# LooRollSensorTop.net
KiCad netlist of a schematic drawn in EAGLE
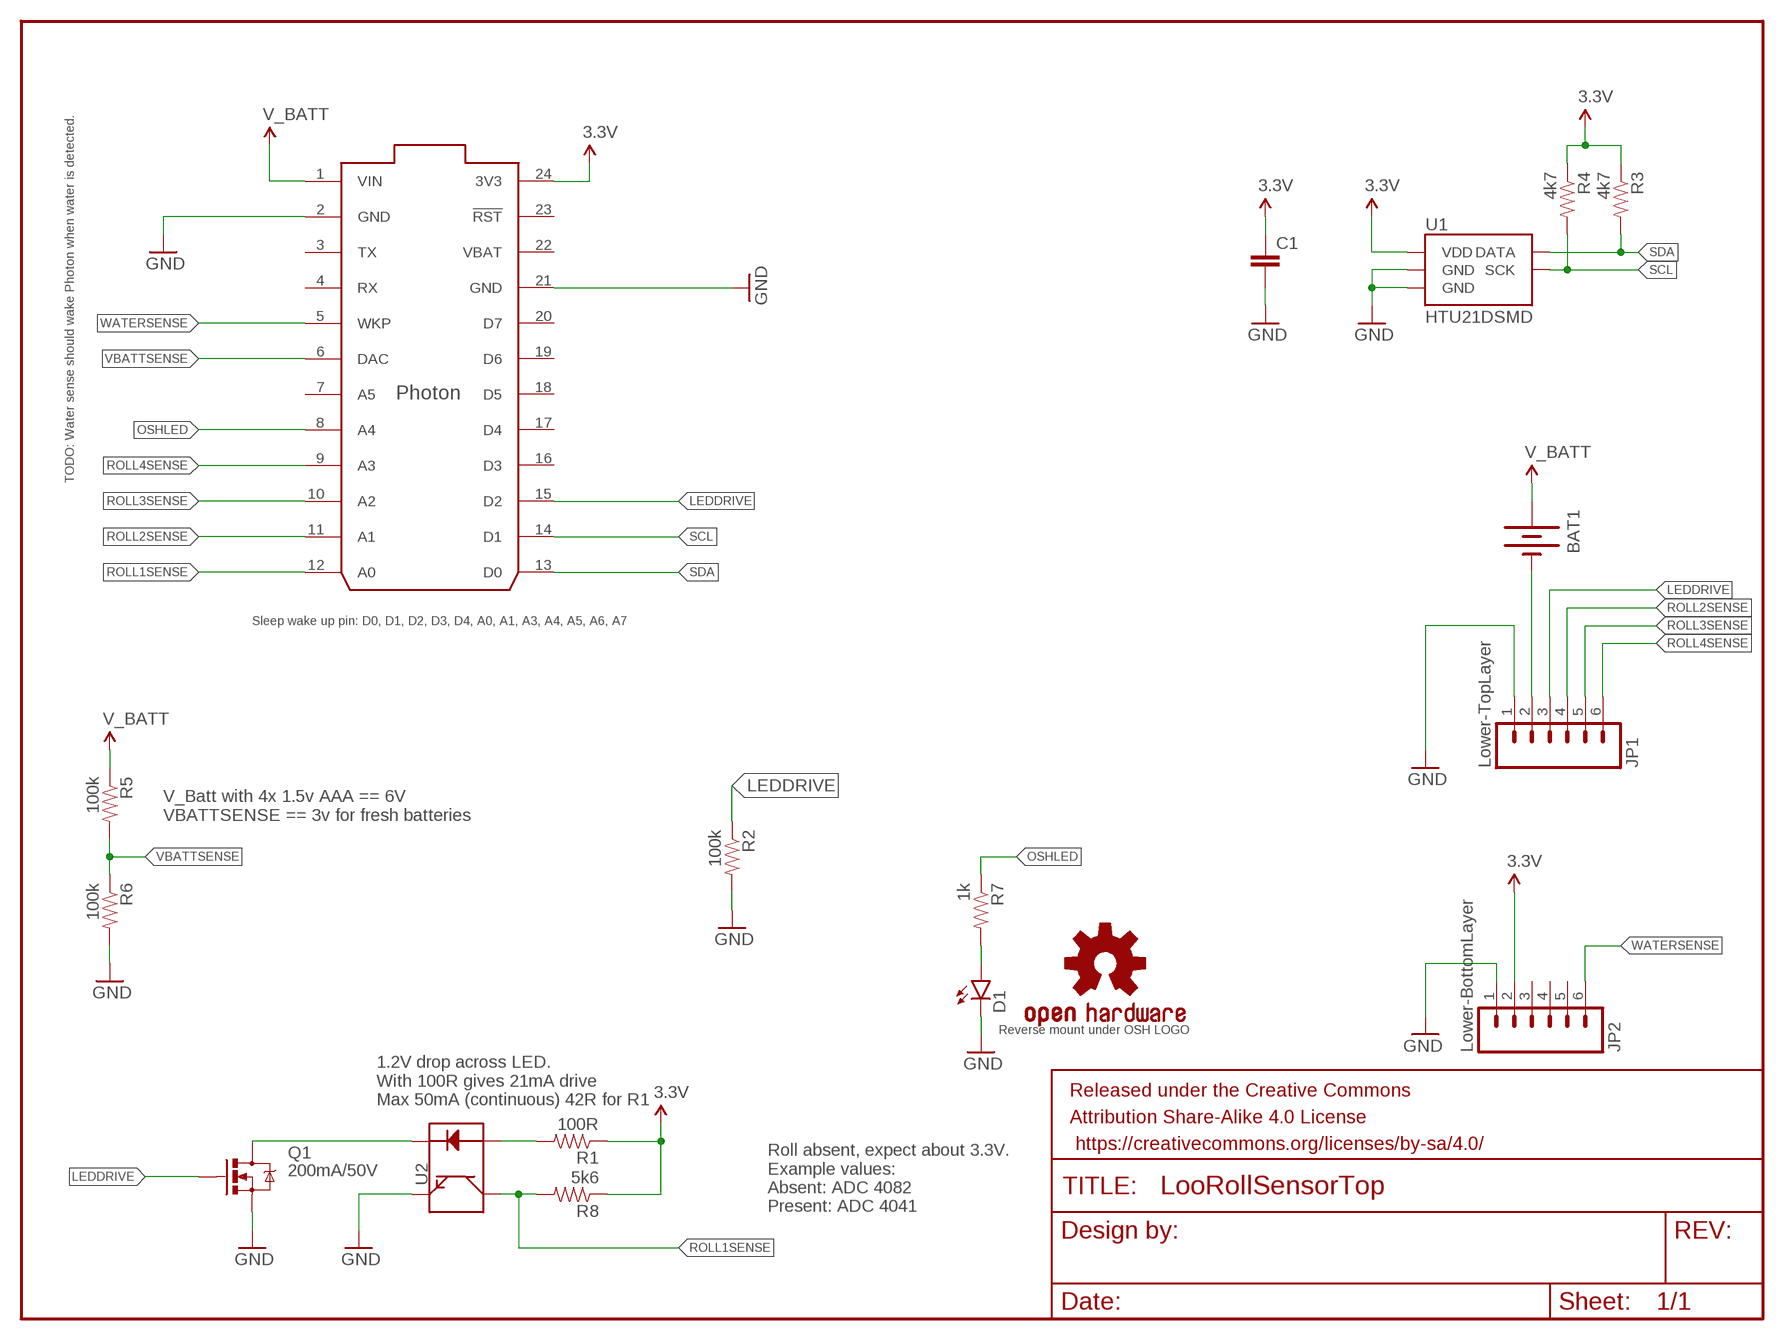
[diagram p0: schematic, sheet 1]

(export (version "E")
  (design (tool "Eeschema 10.0.6"))
  (components
    (comp (ref "BAT1")
      (value "BATTERYAA-PANEL")
      (footprint "eagle-import:BATTERY-AA-PANEL")
      (libsource (lib "eagle-import") (part "BATTERYAA-PANEL"))
    )
    (comp (ref "C1")
      (value "CAP0805")
      (footprint "eagle-import:0805")
      (libsource (lib "eagle-import") (part "CAP0805"))
    )
    (comp (ref "D1")
      (value "LED1206-BOTTOM")
      (footprint "eagle-import:LED-1206-BOTTOM")
      (libsource (lib "eagle-import") (part "LED1206-BOTTOM"))
    )
    (comp (ref "FRAME1")
      (value "FRAME-LETTER")
      (footprint "eagle-import:CREATIVE_COMMONS")
      (libsource (lib "eagle-import") (part "FRAME-LETTER"))
    )
    (comp (ref "JP1")
      (value "Lower-TopLayer")
      (footprint "eagle-import:1X06-SMD_EDGE")
      (libsource (lib "eagle-import") (part "M061X06-SMD-EDGE-SOLDERLINK1X06-SMD-EDGE-SOLDERLINK"))
    )
    (comp (ref "JP2")
      (value "Lower-BottomLayer")
      (footprint "eagle-import:1X06-SMD_EDGE")
      (libsource (lib "eagle-import") (part "M061X06-SMD-EDGE-SOLDERLINK1X06-SMD-EDGE-SOLDERLINK"))
    )
    (comp (ref "LOGO1")
      (value "OSHW-LOGOM")
      (footprint "eagle-import:OSHW-LOGO-M")
      (libsource (lib "eagle-import") (part "OSHW-LOGOM"))
    )
    (comp (ref "Q1")
      (value "200mA/50V")
      (footprint "eagle-import:SOT23-3")
      (libsource (lib "eagle-import") (part "MOSFET-NCHANNELBSS138"))
    )
    (comp (ref "R1")
      (value "100R")
      (footprint "eagle-import:1206")
      (libsource (lib "eagle-import") (part "RESISTOR1206"))
    )
    (comp (ref "R2")
      (value "100k")
      (footprint "eagle-import:1206")
      (libsource (lib "eagle-import") (part "RESISTOR1206"))
    )
    (comp (ref "R3")
      (value "4k7")
      (footprint "eagle-import:1206")
      (libsource (lib "eagle-import") (part "RESISTOR1206"))
    )
    (comp (ref "R4")
      (value "4k7")
      (footprint "eagle-import:1206")
      (libsource (lib "eagle-import") (part "RESISTOR1206"))
    )
    (comp (ref "R5")
      (value "100k")
      (footprint "eagle-import:1206")
      (libsource (lib "eagle-import") (part "RESISTOR1206"))
    )
    (comp (ref "R6")
      (value "100k")
      (footprint "eagle-import:1206")
      (libsource (lib "eagle-import") (part "RESISTOR1206"))
    )
    (comp (ref "R7")
      (value "1k")
      (footprint "eagle-import:1206")
      (libsource (lib "eagle-import") (part "RESISTOR1206"))
    )
    (comp (ref "R8")
      (value "5k6")
      (footprint "eagle-import:1206")
      (libsource (lib "eagle-import") (part "RESISTOR1206"))
    )
    (comp (ref "U$1")
      (value "PHOTON_WITH_HEADERS")
      (footprint "eagle-import:PHOTON")
      (libsource (lib "eagle-import") (part "PHOTON_WITH_HEADERS"))
    )
    (comp (ref "U1")
      (value "HTU21DSMD")
      (footprint "eagle-import:HTU21D")
      (libsource (lib "eagle-import") (part "HTU21DSMD"))
    )
    (comp (ref "U2")
      (value "QRE1113SMD-W")
      (footprint "eagle-import:QRE1113-W")
      (libsource (lib "eagle-import") (part "QRE1113SMD-W"))
    )
  )
  (nets
    (net (code "1") (name "/VBAT") (class "Default")
      (node (ref "U$1") (pin "22") (pinfunction "VBAT_22") (pintype "power_in"))
    )
    (net (code "2") (name "3.3V") (class "Default")
      (node (ref "C1") (pin "1") (pinfunction "1_1") (pintype "passive"))
      (node (ref "JP2") (pin "2") (pinfunction "2_2") (pintype "passive"))
      (node (ref "R1") (pin "1") (pinfunction "1_1") (pintype "passive"))
      (node (ref "R3") (pin "1") (pinfunction "1_1") (pintype "passive"))
      (node (ref "R4") (pin "1") (pinfunction "1_1") (pintype "passive"))
      (node (ref "R8") (pin "1") (pinfunction "1_1") (pintype "passive"))
      (node (ref "U$1") (pin "24") (pinfunction "3V3_24") (pintype "power_in"))
      (node (ref "U1") (pin "VDD") (pinfunction "VDD_VDD") (pintype "power_in"))
    )
    (net (code "3") (name "GND") (class "Default")
      (node (ref "C1") (pin "2") (pinfunction "2_2") (pintype "passive"))
      (node (ref "D1") (pin "C") (pinfunction "C_C") (pintype "passive"))
      (node (ref "JP1") (pin "1") (pinfunction "1_1") (pintype "passive"))
      (node (ref "JP2") (pin "1") (pinfunction "1_1") (pintype "passive"))
      (node (ref "Q1") (pin "2") (pinfunction "S_2") (pintype "passive"))
      (node (ref "R2") (pin "2") (pinfunction "2_2") (pintype "passive"))
      (node (ref "R6") (pin "2") (pinfunction "2_2") (pintype "passive"))
      (node (ref "U$1") (pin "2") (pinfunction "GND_2") (pintype "power_in"))
      (node (ref "U$1") (pin "21") (pinfunction "GND_21") (pintype "power_in"))
      (node (ref "U1") (pin "7") (pinfunction "GND_7") (pintype "power_in"))
      (node (ref "U1") (pin "GND") (pinfunction "GND_GND") (pintype "power_in"))
      (node (ref "U2") (pin "4") (pinfunction "E_4") (pintype "bidirectional"))
    )
    (net (code "4") (name "LEDDRIVE") (class "Default")
      (node (ref "JP1") (pin "3") (pinfunction "3_3") (pintype "passive"))
      (node (ref "Q1") (pin "1") (pinfunction "G_1") (pintype "passive"))
      (node (ref "R2") (pin "1") (pinfunction "1_1") (pintype "passive"))
      (node (ref "U$1") (pin "15") (pinfunction "D2_15") (pintype "bidirectional"))
    )
    (net (code "5") (name "Net-(BAT1-Pad-)") (class "Default")
      (node (ref "BAT1") (pin "-") (pinfunction "-_-") (pintype "power_in"))
      (node (ref "JP1") (pin "2") (pinfunction "2_2") (pintype "passive"))
    )
    (net (code "6") (name "Net-(D1-PadA)") (class "Default")
      (node (ref "D1") (pin "A") (pinfunction "A_A") (pintype "passive"))
      (node (ref "R7") (pin "2") (pinfunction "2_2") (pintype "passive"))
    )
    (net (code "7") (name "Net-(Q1-D)") (class "Default")
      (node (ref "Q1") (pin "3") (pinfunction "D_3") (pintype "passive"))
      (node (ref "U2") (pin "2") (pinfunction "K_2") (pintype "bidirectional"))
    )
    (net (code "8") (name "Net-(U2-A)") (class "Default")
      (node (ref "R1") (pin "2") (pinfunction "2_2") (pintype "passive"))
      (node (ref "U2") (pin "1") (pinfunction "A_1") (pintype "bidirectional"))
    )
    (net (code "9") (name "OSHLED") (class "Default")
      (node (ref "R7") (pin "1") (pinfunction "1_1") (pintype "passive"))
      (node (ref "U$1") (pin "8") (pinfunction "A4_8") (pintype "bidirectional"))
    )
    (net (code "10") (name "ROLL1SENSE") (class "Default")
      (node (ref "R8") (pin "2") (pinfunction "2_2") (pintype "passive"))
      (node (ref "U$1") (pin "12") (pinfunction "A0_12") (pintype "bidirectional"))
      (node (ref "U2") (pin "3") (pinfunction "C_3") (pintype "bidirectional"))
    )
    (net (code "11") (name "ROLL2SENSE") (class "Default")
      (node (ref "JP1") (pin "4") (pinfunction "4_4") (pintype "passive"))
      (node (ref "U$1") (pin "11") (pinfunction "A1_11") (pintype "bidirectional"))
    )
    (net (code "12") (name "ROLL3SENSE") (class "Default")
      (node (ref "JP1") (pin "5") (pinfunction "5_5") (pintype "passive"))
      (node (ref "U$1") (pin "10") (pinfunction "A2_10") (pintype "bidirectional"))
    )
    (net (code "13") (name "ROLL4SENSE") (class "Default")
      (node (ref "JP1") (pin "6") (pinfunction "6_6") (pintype "passive"))
      (node (ref "U$1") (pin "9") (pinfunction "A3_9") (pintype "bidirectional"))
    )
    (net (code "14") (name "SCL") (class "Default")
      (node (ref "R4") (pin "2") (pinfunction "2_2") (pintype "passive"))
      (node (ref "U$1") (pin "14") (pinfunction "D1_14") (pintype "bidirectional"))
      (node (ref "U1") (pin "SCK") (pinfunction "SCK_SCK") (pintype "input"))
    )
    (net (code "15") (name "SDA") (class "Default")
      (node (ref "R3") (pin "2") (pinfunction "2_2") (pintype "passive"))
      (node (ref "U$1") (pin "13") (pinfunction "D0_13") (pintype "bidirectional"))
      (node (ref "U1") (pin "DATA") (pinfunction "DATA_DATA") (pintype "bidirectional"))
    )
    (net (code "16") (name "VBATTSENSE") (class "Default")
      (node (ref "R5") (pin "2") (pinfunction "2_2") (pintype "passive"))
      (node (ref "R6") (pin "1") (pinfunction "1_1") (pintype "passive"))
      (node (ref "U$1") (pin "6") (pinfunction "DAC_6") (pintype "bidirectional"))
    )
    (net (code "17") (name "V_BATT") (class "Default")
      (node (ref "BAT1") (pin "+") (pinfunction "+_+") (pintype "power_in"))
      (node (ref "R5") (pin "1") (pinfunction "1_1") (pintype "passive"))
      (node (ref "U$1") (pin "1") (pinfunction "VIN_1") (pintype "power_in"))
    )
    (net (code "18") (name "WATERSENSE") (class "Default")
      (node (ref "JP2") (pin "6") (pinfunction "6_6") (pintype "passive"))
      (node (ref "U$1") (pin "5") (pinfunction "WKP_5") (pintype "bidirectional"))
    )
    (net (code "19") (name "unconnected-(JP2-Pad3)") (class "Default")
      (node (ref "JP2") (pin "3") (pinfunction "3_3") (pintype "passive"))
    )
    (net (code "20") (name "unconnected-(JP2-Pad4)") (class "Default")
      (node (ref "JP2") (pin "4") (pinfunction "4_4") (pintype "passive"))
    )
    (net (code "21") (name "unconnected-(JP2-Pad5)") (class "Default")
      (node (ref "JP2") (pin "5") (pinfunction "5_5") (pintype "passive"))
    )
    (net (code "22") (name "unconnected-(U$1-A5-Pad7)") (class "Default")
      (node (ref "U$1") (pin "7") (pinfunction "A5_7") (pintype "bidirectional"))
    )
    (net (code "23") (name "unconnected-(U$1-D3-Pad16)") (class "Default")
      (node (ref "U$1") (pin "16") (pinfunction "D3_16") (pintype "bidirectional"))
    )
    (net (code "24") (name "unconnected-(U$1-D4-Pad17)") (class "Default")
      (node (ref "U$1") (pin "17") (pinfunction "D4_17") (pintype "bidirectional"))
    )
    (net (code "25") (name "unconnected-(U$1-D5-Pad18)") (class "Default")
      (node (ref "U$1") (pin "18") (pinfunction "D5_18") (pintype "bidirectional"))
    )
    (net (code "26") (name "unconnected-(U$1-D6-Pad19)") (class "Default")
      (node (ref "U$1") (pin "19") (pinfunction "D6_19") (pintype "bidirectional"))
    )
    (net (code "27") (name "unconnected-(U$1-D7-Pad20)") (class "Default")
      (node (ref "U$1") (pin "20") (pinfunction "D7_20") (pintype "bidirectional"))
    )
    (net (code "28") (name "unconnected-(U$1-RX-Pad4)") (class "Default")
      (node (ref "U$1") (pin "4") (pinfunction "RX_4") (pintype "bidirectional"))
    )
    (net (code "29") (name "unconnected-(U$1-TX-Pad3)") (class "Default")
      (node (ref "U$1") (pin "3") (pinfunction "TX_3") (pintype "bidirectional"))
    )
    (net (code "30") (name "unconnected-(U$1-~{RST}-Pad23)") (class "Default")
      (node (ref "U$1") (pin "23") (pinfunction "~{RST}_23") (pintype "bidirectional"))
    )
  )
)
